# openTPM-v36.net
KiCad netlist of a schematic drawn in EAGLE
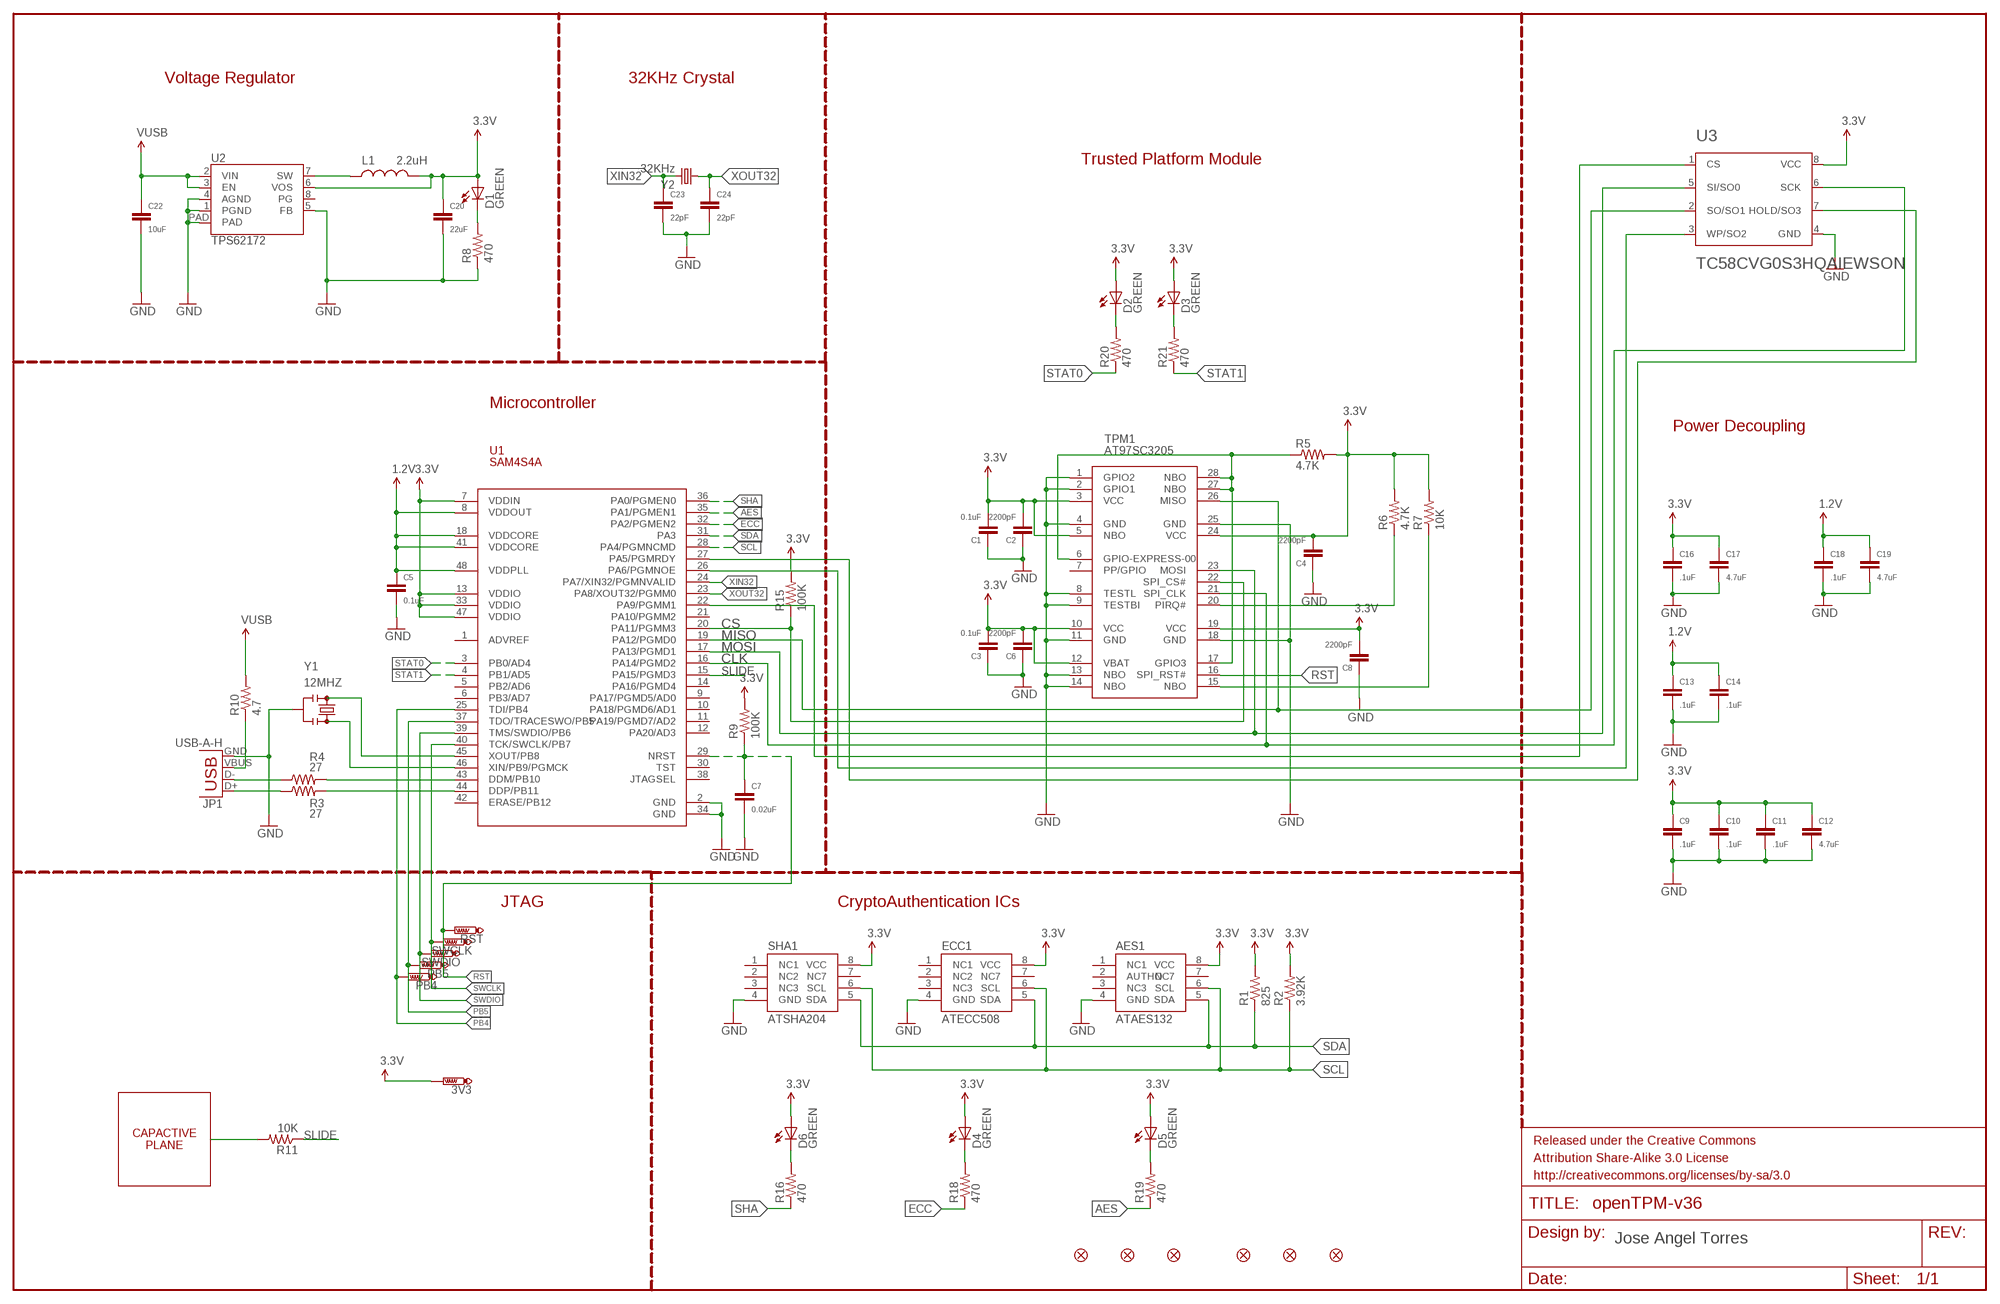
[diagram p0: schematic, sheet 1]

(export (version "E")
  (design (tool "Eeschema 10.0.6"))
  (components
    (comp (ref "3V3")
      (value "PTR1B1,27")
      (footprint "eagle-import:B1,27")
      (libsource (lib "eagle-import") (part "PTR1B1,27"))
    )
    (comp (ref "AES1")
      (value "ATAES132")
      (footprint "eagle-import:CRYPTOTRONIX_SOIC8")
      (libsource (lib "eagle-import") (part "CRYPTOTRONIX_ATAES132"))
    )
    (comp (ref "C1")
      (value "0.1uF")
      (footprint "eagle-import:0402")
      (libsource (lib "eagle-import") (part "CAPACITOR.0402"))
    )
    (comp (ref "C2")
      (value "2200pF")
      (footprint "eagle-import:0402")
      (libsource (lib "eagle-import") (part "CAPACITOR.0402"))
    )
    (comp (ref "C3")
      (value "0.1uF")
      (footprint "eagle-import:0402")
      (libsource (lib "eagle-import") (part "CAPACITOR.0402"))
    )
    (comp (ref "C4")
      (value "2200pF")
      (footprint "eagle-import:0402")
      (libsource (lib "eagle-import") (part "CAPACITOR.0402"))
    )
    (comp (ref "C5")
      (value "0.1uF")
      (footprint "eagle-import:0402")
      (libsource (lib "eagle-import") (part "CAPACITOR.0402"))
    )
    (comp (ref "C6")
      (value "2200pF")
      (footprint "eagle-import:0402")
      (libsource (lib "eagle-import") (part "CAPACITOR.0402"))
    )
    (comp (ref "C7")
      (value "0.02uF")
      (footprint "eagle-import:0402")
      (libsource (lib "eagle-import") (part "CAPACITOR.0402"))
    )
    (comp (ref "C8")
      (value "2200pF")
      (footprint "eagle-import:0402")
      (libsource (lib "eagle-import") (part "CAPACITOR.0402"))
    )
    (comp (ref "C9")
      (value ".1uF")
      (footprint "eagle-import:0402")
      (libsource (lib "eagle-import") (part "CAPACITOR.0402"))
    )
    (comp (ref "C10")
      (value ".1uF")
      (footprint "eagle-import:0402")
      (libsource (lib "eagle-import") (part "CAPACITOR.0402"))
    )
    (comp (ref "C11")
      (value ".1uF")
      (footprint "eagle-import:0402")
      (libsource (lib "eagle-import") (part "CAPACITOR.0402"))
    )
    (comp (ref "C12")
      (value "4.7uF")
      (footprint "eagle-import:0402")
      (libsource (lib "eagle-import") (part "CAPACITOR.0402"))
    )
    (comp (ref "C13")
      (value ".1uF")
      (footprint "eagle-import:0402")
      (libsource (lib "eagle-import") (part "CAPACITOR.0402"))
    )
    (comp (ref "C14")
      (value ".1uF")
      (footprint "eagle-import:0402")
      (libsource (lib "eagle-import") (part "CAPACITOR.0402"))
    )
    (comp (ref "C16")
      (value ".1uF")
      (footprint "eagle-import:0402")
      (libsource (lib "eagle-import") (part "CAPACITOR.0402"))
    )
    (comp (ref "C17")
      (value "4.7uF")
      (footprint "eagle-import:0402")
      (libsource (lib "eagle-import") (part "CAPACITOR.0402"))
    )
    (comp (ref "C18")
      (value ".1uF")
      (footprint "eagle-import:0402")
      (libsource (lib "eagle-import") (part "CAPACITOR.0402"))
    )
    (comp (ref "C19")
      (value "4.7uF")
      (footprint "eagle-import:0402")
      (libsource (lib "eagle-import") (part "CAPACITOR.0402"))
    )
    (comp (ref "C20")
      (value "22uF")
      (footprint "eagle-import:0603")
      (libsource (lib "eagle-import") (part "CAPACITOR.0603"))
    )
    (comp (ref "C22")
      (value "10uF")
      (footprint "eagle-import:0402")
      (libsource (lib "eagle-import") (part "CAPACITOR.0402"))
    )
    (comp (ref "C23")
      (value "22pF")
      (footprint "eagle-import:0402")
      (libsource (lib "eagle-import") (part "CAPACITOR.0402"))
    )
    (comp (ref "C24")
      (value "22pF")
      (footprint "eagle-import:0402")
      (libsource (lib "eagle-import") (part "CAPACITOR.0402"))
    )
    (comp (ref "D1")
      (value "GREEN")
      (footprint "eagle-import:SPARKFUN-LED_LED-0603")
      (libsource (lib "eagle-import") (part "SPARKFUN-LED_LED-GREEN0603"))
    )
    (comp (ref "D2")
      (value "GREEN")
      (footprint "eagle-import:SPARKFUN-LED_LED-0603")
      (libsource (lib "eagle-import") (part "SPARKFUN-LED_LED-GREEN0603"))
    )
    (comp (ref "D3")
      (value "GREEN")
      (footprint "eagle-import:SPARKFUN-LED_LED-0603")
      (libsource (lib "eagle-import") (part "SPARKFUN-LED_LED-GREEN0603"))
    )
    (comp (ref "D4")
      (value "GREEN")
      (footprint "eagle-import:SPARKFUN-LED_LED-0603")
      (libsource (lib "eagle-import") (part "SPARKFUN-LED_LED-GREEN0603"))
    )
    (comp (ref "D5")
      (value "GREEN")
      (footprint "eagle-import:SPARKFUN-LED_LED-0603")
      (libsource (lib "eagle-import") (part "SPARKFUN-LED_LED-GREEN0603"))
    )
    (comp (ref "D6")
      (value "GREEN")
      (footprint "eagle-import:SPARKFUN-LED_LED-0603")
      (libsource (lib "eagle-import") (part "SPARKFUN-LED_LED-GREEN0603"))
    )
    (comp (ref "ECC1")
      (value "ATECC508")
      (footprint "eagle-import:CRYPTOTRONIX_SOIC8")
      (libsource (lib "eagle-import") (part "ATECC508"))
    )
    (comp (ref "FID1")
      (value "SPARKFUN-AESTHETICS_FIDUCIAL1X2")
      (footprint "eagle-import:SPARKFUN-AESTHETICS_FIDUCIAL-1X2")
      (libsource (lib "eagle-import") (part "SPARKFUN-AESTHETICS_FIDUCIAL1X2"))
    )
    (comp (ref "FID2")
      (value "SPARKFUN-AESTHETICS_FIDUCIAL1X2")
      (footprint "eagle-import:SPARKFUN-AESTHETICS_FIDUCIAL-1X2")
      (libsource (lib "eagle-import") (part "SPARKFUN-AESTHETICS_FIDUCIAL1X2"))
    )
    (comp (ref "FID3")
      (value "SPARKFUN-AESTHETICS_FIDUCIAL1X2")
      (footprint "eagle-import:SPARKFUN-AESTHETICS_FIDUCIAL-1X2")
      (libsource (lib "eagle-import") (part "SPARKFUN-AESTHETICS_FIDUCIAL1X2"))
    )
    (comp (ref "FID4")
      (value "SPARKFUN-AESTHETICS_FIDUCIAL1X2")
      (footprint "eagle-import:SPARKFUN-AESTHETICS_FIDUCIAL-1X2")
      (libsource (lib "eagle-import") (part "SPARKFUN-AESTHETICS_FIDUCIAL1X2"))
    )
    (comp (ref "FID5")
      (value "SPARKFUN-AESTHETICS_FIDUCIAL1X2")
      (footprint "eagle-import:SPARKFUN-AESTHETICS_FIDUCIAL-1X2")
      (libsource (lib "eagle-import") (part "SPARKFUN-AESTHETICS_FIDUCIAL1X2"))
    )
    (comp (ref "FID6")
      (value "SPARKFUN-AESTHETICS_FIDUCIAL1X2")
      (footprint "eagle-import:SPARKFUN-AESTHETICS_FIDUCIAL-1X2")
      (libsource (lib "eagle-import") (part "SPARKFUN-AESTHETICS_FIDUCIAL1X2"))
    )
    (comp (ref "JP1")
      (value "USB-A-H")
      (footprint "eagle-import:USB-A-H")
      (libsource (lib "eagle-import") (part "USB-A-H"))
    )
    (comp (ref "L1")
      (value "2.2uH")
      (footprint "eagle-import:C0402")
      (libsource (lib "eagle-import") (part "INDUCTOR0402"))
    )
    (comp (ref "PB4")
      (value "PTR1B1,27")
      (footprint "eagle-import:B1,27")
      (libsource (lib "eagle-import") (part "PTR1B1,27"))
    )
    (comp (ref "PB5")
      (value "PTR1B1,27")
      (footprint "eagle-import:B1,27")
      (libsource (lib "eagle-import") (part "PTR1B1,27"))
    )
    (comp (ref "R1")
      (value "825")
      (footprint "eagle-import:0402")
      (libsource (lib "eagle-import") (part "RESISTOR.0402"))
    )
    (comp (ref "R2")
      (value "3.92K")
      (footprint "eagle-import:0402")
      (libsource (lib "eagle-import") (part "RESISTOR.0402"))
    )
    (comp (ref "R3")
      (value "27")
      (footprint "eagle-import:0402")
      (libsource (lib "eagle-import") (part "RESISTOR.0402"))
    )
    (comp (ref "R4")
      (value "27")
      (footprint "eagle-import:0402")
      (libsource (lib "eagle-import") (part "RESISTOR.0402"))
    )
    (comp (ref "R5")
      (value "4.7K")
      (footprint "eagle-import:0402")
      (libsource (lib "eagle-import") (part "RESISTOR.0402"))
    )
    (comp (ref "R6")
      (value "4.7K")
      (footprint "eagle-import:0402")
      (libsource (lib "eagle-import") (part "RESISTOR.0402"))
    )
    (comp (ref "R7")
      (value "10K")
      (footprint "eagle-import:0402")
      (libsource (lib "eagle-import") (part "RESISTOR.0402"))
    )
    (comp (ref "R8")
      (value "470")
      (footprint "eagle-import:0402")
      (libsource (lib "eagle-import") (part "RESISTOR.0402"))
    )
    (comp (ref "R9")
      (value "100K")
      (footprint "eagle-import:0402")
      (libsource (lib "eagle-import") (part "RESISTOR.0402"))
    )
    (comp (ref "R10")
      (value "4.7")
      (footprint "eagle-import:0402")
      (libsource (lib "eagle-import") (part "RESISTOR.0402"))
    )
    (comp (ref "R11")
      (value "10K")
      (footprint "eagle-import:0402")
      (libsource (lib "eagle-import") (part "RESISTOR.0402"))
    )
    (comp (ref "R15")
      (value "100K")
      (footprint "eagle-import:0402")
      (libsource (lib "eagle-import") (part "RESISTOR.0402"))
    )
    (comp (ref "R16")
      (value "470")
      (footprint "eagle-import:0402")
      (libsource (lib "eagle-import") (part "RESISTOR.0402"))
    )
    (comp (ref "R18")
      (value "470")
      (footprint "eagle-import:0402")
      (libsource (lib "eagle-import") (part "RESISTOR.0402"))
    )
    (comp (ref "R19")
      (value "470")
      (footprint "eagle-import:0402")
      (libsource (lib "eagle-import") (part "RESISTOR.0402"))
    )
    (comp (ref "R20")
      (value "470")
      (footprint "eagle-import:0402")
      (libsource (lib "eagle-import") (part "RESISTOR.0402"))
    )
    (comp (ref "R21")
      (value "470")
      (footprint "eagle-import:0402")
      (libsource (lib "eagle-import") (part "RESISTOR.0402"))
    )
    (comp (ref "RST")
      (value "PTR1B1,27")
      (footprint "eagle-import:B1,27")
      (libsource (lib "eagle-import") (part "PTR1B1,27"))
    )
    (comp (ref "SHA1")
      (value "ATSHA204")
      (footprint "eagle-import:CRYPTOTRONIX_SOIC8")
      (libsource (lib "eagle-import") (part "CRYPTOTRONIX_ATSHA204"))
    )
    (comp (ref "SWCLK")
      (value "PTR1B1,27")
      (footprint "eagle-import:B1,27")
      (libsource (lib "eagle-import") (part "PTR1B1,27"))
    )
    (comp (ref "SWDIO")
      (value "PTR1B1,27")
      (footprint "eagle-import:B1,27")
      (libsource (lib "eagle-import") (part "PTR1B1,27"))
    )
    (comp (ref "TPM1")
      (value "AT97SC3205")
      (footprint "eagle-import:TSSOP28")
      (libsource (lib "eagle-import") (part "AT97SC3205"))
    )
    (comp (ref "U1")
      (value "SAM4S4A")
      (footprint "eagle-import:LQFP-48")
      (libsource (lib "eagle-import") (part "SAM4S4A"))
    )
    (comp (ref "U2")
      (value "TPS62172")
      (footprint "eagle-import:WSON-8-PAD")
      (libsource (lib "eagle-import") (part "TPS62172"))
    )
    (comp (ref "U3")
      (value "TC58CVG0S3HQAIEWSON")
      (footprint "eagle-import:WSON-8-PAD")
      (libsource (lib "eagle-import") (part "TC58CVG0S3HQAIEWSON"))
    )
    (comp (ref "Y1")
      (value "12MHZ")
      (footprint "eagle-import:RESONATOR-SMD")
      (libsource (lib "eagle-import") (part "RESONATOR12MHZ"))
    )
    (comp (ref "Y2")
      (value "32KHz")
      (footprint "eagle-import:CRYSTAL-32KHZ-SMD_EPSON_MC146")
      (libsource (lib "eagle-import") (part "CRYSTALEPSONMC146"))
    )
  )
  (nets
    (net (code "1") (name "/CLK") (class "Default")
      (node (ref "TPM1") (pin "21") (pinfunction "SPI_CLK_21") (pintype "bidirectional"))
      (node (ref "U1") (pin "16") (pinfunction "PA14/PGMD2_16") (pintype "bidirectional"))
      (node (ref "U3") (pin "6") (pinfunction "SCK_6") (pintype "bidirectional"))
    )
    (net (code "2") (name "/CS") (class "Default")
      (node (ref "R15") (pin "1") (pinfunction "1_1") (pintype "passive"))
      (node (ref "TPM1") (pin "22") (pinfunction "SPI_CS#_22") (pintype "power_in"))
      (node (ref "U1") (pin "20") (pinfunction "PA11/PGMM3_20") (pintype "bidirectional"))
    )
    (net (code "3") (name "/MISO") (class "Default")
      (node (ref "TPM1") (pin "26") (pinfunction "MISO_26") (pintype "power_in"))
      (node (ref "U1") (pin "19") (pinfunction "PA12/PGMD0_19") (pintype "bidirectional"))
      (node (ref "U3") (pin "2") (pinfunction "SO/SO1_2") (pintype "bidirectional"))
    )
    (net (code "4") (name "/MOSI") (class "Default")
      (node (ref "TPM1") (pin "23") (pinfunction "MOSI_23") (pintype "power_in"))
      (node (ref "U1") (pin "17") (pinfunction "PA13/PGMD1_17") (pintype "bidirectional"))
      (node (ref "U3") (pin "5") (pinfunction "SI/SO0_5") (pintype "bidirectional"))
    )
    (net (code "5") (name "/SLIDE") (class "Default")
      (node (ref "R11") (pin "1") (pinfunction "1_1") (pintype "passive"))
      (node (ref "U1") (pin "15") (pinfunction "PA15/PGMD3_15") (pintype "bidirectional"))
    )
    (net (code "6") (name "1.2V") (class "Default")
      (node (ref "C13") (pin "1") (pinfunction "1_1") (pintype "passive"))
      (node (ref "C14") (pin "1") (pinfunction "1_1") (pintype "passive"))
      (node (ref "C18") (pin "1") (pinfunction "1_1") (pintype "passive"))
      (node (ref "C19") (pin "1") (pinfunction "1_1") (pintype "passive"))
      (node (ref "C5") (pin "1") (pinfunction "1_1") (pintype "passive"))
      (node (ref "U1") (pin "18") (pinfunction "VDDCORE_18") (pintype "bidirectional"))
      (node (ref "U1") (pin "41") (pinfunction "VDDCORE_41") (pintype "bidirectional"))
      (node (ref "U1") (pin "48") (pinfunction "VDDPLL_48") (pintype "bidirectional"))
      (node (ref "U1") (pin "8") (pinfunction "VDDOUT_8") (pintype "bidirectional"))
    )
    (net (code "7") (name "3.3V") (class "Default")
      (node (ref "3V3") (pin "TP") (pinfunction "TP_TP") (pintype "input"))
      (node (ref "AES1") (pin "8") (pinfunction "VCC_8") (pintype "power_in"))
      (node (ref "C1") (pin "2") (pinfunction "2_2") (pintype "passive"))
      (node (ref "C10") (pin "1") (pinfunction "1_1") (pintype "passive"))
      (node (ref "C11") (pin "1") (pinfunction "1_1") (pintype "passive"))
      (node (ref "C12") (pin "1") (pinfunction "1_1") (pintype "passive"))
      (node (ref "C16") (pin "1") (pinfunction "1_1") (pintype "passive"))
      (node (ref "C17") (pin "1") (pinfunction "1_1") (pintype "passive"))
      (node (ref "C2") (pin "2") (pinfunction "2_2") (pintype "passive"))
      (node (ref "C20") (pin "1") (pinfunction "1_1") (pintype "passive"))
      (node (ref "C3") (pin "2") (pinfunction "2_2") (pintype "passive"))
      (node (ref "C4") (pin "2") (pinfunction "2_2") (pintype "passive"))
      (node (ref "C6") (pin "2") (pinfunction "2_2") (pintype "passive"))
      (node (ref "C8") (pin "2") (pinfunction "2_2") (pintype "passive"))
      (node (ref "C9") (pin "1") (pinfunction "1_1") (pintype "passive"))
      (node (ref "D1") (pin "A") (pinfunction "A_A") (pintype "passive"))
      (node (ref "D2") (pin "A") (pinfunction "A_A") (pintype "passive"))
      (node (ref "D3") (pin "A") (pinfunction "A_A") (pintype "passive"))
      (node (ref "D4") (pin "A") (pinfunction "A_A") (pintype "passive"))
      (node (ref "D5") (pin "A") (pinfunction "A_A") (pintype "passive"))
      (node (ref "D6") (pin "A") (pinfunction "A_A") (pintype "passive"))
      (node (ref "ECC1") (pin "8") (pinfunction "VCC_8") (pintype "power_in"))
      (node (ref "L1") (pin "2") (pinfunction "2_2") (pintype "passive"))
      (node (ref "R1") (pin "2") (pinfunction "2_2") (pintype "passive"))
      (node (ref "R15") (pin "2") (pinfunction "2_2") (pintype "passive"))
      (node (ref "R2") (pin "2") (pinfunction "2_2") (pintype "passive"))
      (node (ref "R5") (pin "2") (pinfunction "2_2") (pintype "passive"))
      (node (ref "R6") (pin "2") (pinfunction "2_2") (pintype "passive"))
      (node (ref "R7") (pin "2") (pinfunction "2_2") (pintype "passive"))
      (node (ref "R9") (pin "2") (pinfunction "2_2") (pintype "passive"))
      (node (ref "SHA1") (pin "8") (pinfunction "VCC_8") (pintype "power_in"))
      (node (ref "TPM1") (pin "10") (pinfunction "VCC_10") (pintype "power_in"))
      (node (ref "TPM1") (pin "12") (pinfunction "VBAT_12") (pintype "bidirectional"))
      (node (ref "TPM1") (pin "19") (pinfunction "VCC_19") (pintype "power_in"))
      (node (ref "TPM1") (pin "24") (pinfunction "VCC_24") (pintype "power_in"))
      (node (ref "TPM1") (pin "3") (pinfunction "VCC_3") (pintype "power_in"))
      (node (ref "TPM1") (pin "5") (pinfunction "NBO_5") (pintype "bidirectional"))
      (node (ref "U1") (pin "13") (pinfunction "VDDIO_13") (pintype "bidirectional"))
      (node (ref "U1") (pin "33") (pinfunction "VDDIO_33") (pintype "bidirectional"))
      (node (ref "U1") (pin "47") (pinfunction "VDDIO_47") (pintype "bidirectional"))
      (node (ref "U1") (pin "7") (pinfunction "VDDIN_7") (pintype "bidirectional"))
      (node (ref "U2") (pin "6") (pinfunction "VOS_6") (pintype "bidirectional"))
      (node (ref "U3") (pin "8") (pinfunction "VCC_8") (pintype "bidirectional"))
    )
    (net (code "8") (name "AES") (class "Default")
      (node (ref "R19") (pin "1") (pinfunction "1_1") (pintype "passive"))
      (node (ref "U1") (pin "35") (pinfunction "PA1/PGMEN1_35") (pintype "bidirectional"))
    )
    (net (code "9") (name "ECC") (class "Default")
      (node (ref "R18") (pin "1") (pinfunction "1_1") (pintype "passive"))
      (node (ref "U1") (pin "32") (pinfunction "PA2/PGMEN2_32") (pintype "bidirectional"))
    )
    (net (code "10") (name "GND") (class "Default")
      (node (ref "AES1") (pin "4") (pinfunction "GND_4") (pintype "power_in"))
      (node (ref "C1") (pin "1") (pinfunction "1_1") (pintype "passive"))
      (node (ref "C10") (pin "2") (pinfunction "2_2") (pintype "passive"))
      (node (ref "C11") (pin "2") (pinfunction "2_2") (pintype "passive"))
      (node (ref "C12") (pin "2") (pinfunction "2_2") (pintype "passive"))
      (node (ref "C13") (pin "2") (pinfunction "2_2") (pintype "passive"))
      (node (ref "C14") (pin "2") (pinfunction "2_2") (pintype "passive"))
      (node (ref "C16") (pin "2") (pinfunction "2_2") (pintype "passive"))
      (node (ref "C17") (pin "2") (pinfunction "2_2") (pintype "passive"))
      (node (ref "C18") (pin "2") (pinfunction "2_2") (pintype "passive"))
      (node (ref "C19") (pin "2") (pinfunction "2_2") (pintype "passive"))
      (node (ref "C2") (pin "1") (pinfunction "1_1") (pintype "passive"))
      (node (ref "C20") (pin "2") (pinfunction "2_2") (pintype "passive"))
      (node (ref "C22") (pin "2") (pinfunction "2_2") (pintype "passive"))
      (node (ref "C23") (pin "2") (pinfunction "2_2") (pintype "passive"))
      (node (ref "C24") (pin "2") (pinfunction "2_2") (pintype "passive"))
      (node (ref "C3") (pin "1") (pinfunction "1_1") (pintype "passive"))
      (node (ref "C4") (pin "1") (pinfunction "1_1") (pintype "passive"))
      (node (ref "C5") (pin "2") (pinfunction "2_2") (pintype "passive"))
      (node (ref "C6") (pin "1") (pinfunction "1_1") (pintype "passive"))
      (node (ref "C7") (pin "2") (pinfunction "2_2") (pintype "passive"))
      (node (ref "C8") (pin "1") (pinfunction "1_1") (pintype "passive"))
      (node (ref "C9") (pin "2") (pinfunction "2_2") (pintype "passive"))
      (node (ref "ECC1") (pin "4") (pinfunction "GND_4") (pintype "power_in"))
      (node (ref "JP1") (pin "GND") (pinfunction "GND_GND") (pintype "bidirectional"))
      (node (ref "R8") (pin "1") (pinfunction "1_1") (pintype "passive"))
      (node (ref "SHA1") (pin "4") (pinfunction "GND_4") (pintype "power_in"))
      (node (ref "TPM1") (pin "1") (pinfunction "GPIO2_1") (pintype "bidirectional"))
      (node (ref "TPM1") (pin "11") (pinfunction "GND_11") (pintype "power_in"))
      (node (ref "TPM1") (pin "13") (pinfunction "NBO_13") (pintype "bidirectional"))
      (node (ref "TPM1") (pin "14") (pinfunction "NBO_14") (pintype "bidirectional"))
      (node (ref "TPM1") (pin "18") (pinfunction "GND_18") (pintype "power_in"))
      (node (ref "TPM1") (pin "2") (pinfunction "GPIO1_2") (pintype "bidirectional"))
      (node (ref "TPM1") (pin "25") (pinfunction "GND_25") (pintype "power_in"))
      (node (ref "TPM1") (pin "4") (pinfunction "GND_4") (pintype "power_in"))
      (node (ref "TPM1") (pin "8") (pinfunction "TESTL_8") (pintype "bidirectional"))
      (node (ref "TPM1") (pin "9") (pinfunction "TESTBI_9") (pintype "bidirectional"))
      (node (ref "U1") (pin "2") (pinfunction "GND_2") (pintype "bidirectional"))
      (node (ref "U1") (pin "34") (pinfunction "GND_34") (pintype "bidirectional"))
      (node (ref "U2") (pin "1") (pinfunction "PGND_1") (pintype "bidirectional"))
      (node (ref "U2") (pin "4") (pinfunction "AGND_4") (pintype "bidirectional"))
      (node (ref "U2") (pin "5") (pinfunction "FB_5") (pintype "bidirectional"))
      (node (ref "U2") (pin "PAD") (pinfunction "PAD_PAD") (pintype "bidirectional"))
      (node (ref "U3") (pin "4") (pinfunction "GND_4") (pintype "bidirectional"))
      (node (ref "Y1") (pin "2") (pinfunction "2_2") (pintype "passive"))
    )
    (net (code "11") (name "Net-(D1-PadC)") (class "Default")
      (node (ref "D1") (pin "C") (pinfunction "C_C") (pintype "passive"))
      (node (ref "R8") (pin "2") (pinfunction "2_2") (pintype "passive"))
    )
    (net (code "12") (name "Net-(D2-PadC)") (class "Default")
      (node (ref "D2") (pin "C") (pinfunction "C_C") (pintype "passive"))
      (node (ref "R20") (pin "2") (pinfunction "2_2") (pintype "passive"))
    )
    (net (code "13") (name "Net-(D3-PadC)") (class "Default")
      (node (ref "D3") (pin "C") (pinfunction "C_C") (pintype "passive"))
      (node (ref "R21") (pin "2") (pinfunction "2_2") (pintype "passive"))
    )
    (net (code "14") (name "Net-(D4-PadC)") (class "Default")
      (node (ref "D4") (pin "C") (pinfunction "C_C") (pintype "passive"))
      (node (ref "R18") (pin "2") (pinfunction "2_2") (pintype "passive"))
    )
    (net (code "15") (name "Net-(D5-PadC)") (class "Default")
      (node (ref "D5") (pin "C") (pinfunction "C_C") (pintype "passive"))
      (node (ref "R19") (pin "2") (pinfunction "2_2") (pintype "passive"))
    )
    (net (code "16") (name "Net-(D6-PadC)") (class "Default")
      (node (ref "D6") (pin "C") (pinfunction "C_C") (pintype "passive"))
      (node (ref "R16") (pin "2") (pinfunction "2_2") (pintype "passive"))
    )
    (net (code "17") (name "Net-(JP1-PadD+)") (class "Default")
      (node (ref "JP1") (pin "D+") (pinfunction "D+_D+") (pintype "bidirectional"))
      (node (ref "R3") (pin "1") (pinfunction "1_1") (pintype "passive"))
    )
    (net (code "18") (name "Net-(JP1-PadD-)") (class "Default")
      (node (ref "JP1") (pin "D-") (pinfunction "D-_D-") (pintype "bidirectional"))
      (node (ref "R4") (pin "1") (pinfunction "1_1") (pintype "passive"))
    )
    (net (code "19") (name "Net-(JP1-PadVBUS)") (class "Default")
      (node (ref "JP1") (pin "VBUS") (pinfunction "VBUS_VBUS") (pintype "bidirectional"))
      (node (ref "R10") (pin "1") (pinfunction "1_1") (pintype "passive"))
    )
    (net (code "20") (name "Net-(R7-Pad1)") (class "Default")
      (node (ref "R7") (pin "1") (pinfunction "1_1") (pintype "passive"))
      (node (ref "TPM1") (pin "15") (pinfunction "NBO_15") (pintype "bidirectional"))
    )
    (net (code "21") (name "Net-(TPM1-GPIO-EXPRESS-00)") (class "Default")
      (node (ref "R5") (pin "1") (pinfunction "1_1") (pintype "passive"))
      (node (ref "TPM1") (pin "17") (pinfunction "GPIO3_17") (pintype "power_in"))
      (node (ref "TPM1") (pin "27") (pinfunction "NBO_27") (pintype "bidirectional"))
      (node (ref "TPM1") (pin "28") (pinfunction "NBO_28") (pintype "bidirectional"))
      (node (ref "TPM1") (pin "6") (pinfunction "GPIO-EXPRESS-00_6") (pintype "power_in"))
    )
    (net (code "22") (name "Net-(TPM1-PIRQ#)") (class "Default")
      (node (ref "R6") (pin "1") (pinfunction "1_1") (pintype "passive"))
      (node (ref "TPM1") (pin "20") (pinfunction "PIRQ#_20") (pintype "power_in"))
    )
    (net (code "23") (name "Net-(U1-DDM{slash}PB10)") (class "Default")
      (node (ref "R4") (pin "2") (pinfunction "2_2") (pintype "passive"))
      (node (ref "U1") (pin "43") (pinfunction "DDM/PB10_43") (pintype "bidirectional"))
    )
    (net (code "24") (name "Net-(U1-DDP{slash}PB11)") (class "Default")
      (node (ref "R3") (pin "2") (pinfunction "2_2") (pintype "passive"))
      (node (ref "U1") (pin "44") (pinfunction "DDP/PB11_44") (pintype "bidirectional"))
    )
    (net (code "25") (name "Net-(U1-PA5{slash}PGMRDY)") (class "Default")
      (node (ref "U1") (pin "27") (pinfunction "PA5/PGMRDY_27") (pintype "bidirectional"))
      (node (ref "U3") (pin "7") (pinfunction "HOLD/SO3_7") (pintype "bidirectional"))
    )
    (net (code "26") (name "Net-(U1-PA6{slash}PGMNOE)") (class "Default")
      (node (ref "U1") (pin "26") (pinfunction "PA6/PGMNOE_26") (pintype "bidirectional"))
      (node (ref "U3") (pin "3") (pinfunction "WP/SO2_3") (pintype "bidirectional"))
    )
    (net (code "27") (name "Net-(U1-PA9{slash}PGMM1)") (class "Default")
      (node (ref "U1") (pin "22") (pinfunction "PA9/PGMM1_22") (pintype "bidirectional"))
      (node (ref "U3") (pin "1") (pinfunction "CS_1") (pintype "bidirectional"))
    )
    (net (code "28") (name "Net-(U1-XIN{slash}PB9{slash}PGMCK)") (class "Default")
      (node (ref "U1") (pin "46") (pinfunction "XIN/PB9/PGMCK_46") (pintype "bidirectional"))
      (node (ref "Y1") (pin "3") (pinfunction "3_3") (pintype "passive"))
    )
    (net (code "29") (name "Net-(U1-XOUT{slash}PB8)") (class "Default")
      (node (ref "U1") (pin "45") (pinfunction "XOUT/PB8_45") (pintype "bidirectional"))
      (node (ref "Y1") (pin "1") (pinfunction "1_1") (pintype "passive"))
    )
    (net (code "30") (name "Net-(U2-SW)") (class "Default")
      (node (ref "L1") (pin "1") (pinfunction "1_1") (pintype "passive"))
      (node (ref "U2") (pin "7") (pinfunction "SW_7") (pintype "bidirectional"))
    )
    (net (code "31") (name "PB4") (class "Default")
      (node (ref "PB4") (pin "TP") (pinfunction "TP_TP") (pintype "input"))
      (node (ref "U1") (pin "25") (pinfunction "TDI/PB4_25") (pintype "bidirectional"))
    )
    (net (code "32") (name "PB5") (class "Default")
      (node (ref "PB5") (pin "TP") (pinfunction "TP_TP") (pintype "input"))
      (node (ref "U1") (pin "37") (pinfunction "TDO/TRACESWO/PB5_37") (pintype "bidirectional"))
    )
    (net (code "33") (name "RST") (class "Default")
      (node (ref "C7") (pin "1") (pinfunction "1_1") (pintype "passive"))
      (node (ref "R9") (pin "1") (pinfunction "1_1") (pintype "passive"))
      (node (ref "RST") (pin "TP") (pinfunction "TP_TP") (pintype "input"))
      (node (ref "TPM1") (pin "16") (pinfunction "SPI_RST#_16") (pintype "bidirectional"))
      (node (ref "U1") (pin "29") (pinfunction "NRST_29") (pintype "bidirectional"))
    )
    (net (code "34") (name "SCL") (class "Default")
      (node (ref "AES1") (pin "6") (pinfunction "SCL_6") (pintype "bidirectional"))
      (node (ref "ECC1") (pin "6") (pinfunction "SCL_6") (pintype "bidirectional"))
      (node (ref "R2") (pin "1") (pinfunction "1_1") (pintype "passive"))
      (node (ref "SHA1") (pin "6") (pinfunction "SCL_6") (pintype "bidirectional"))
      (node (ref "U1") (pin "28") (pinfunction "PA4/PGMNCMD_28") (pintype "bidirectional"))
    )
    (net (code "35") (name "SDA") (class "Default")
      (node (ref "AES1") (pin "5") (pinfunction "SDA_5") (pintype "bidirectional"))
      (node (ref "ECC1") (pin "5") (pinfunction "SDA_5") (pintype "bidirectional"))
      (node (ref "R1") (pin "1") (pinfunction "1_1") (pintype "passive"))
      (node (ref "SHA1") (pin "5") (pinfunction "SDA_5") (pintype "bidirectional"))
      (node (ref "U1") (pin "31") (pinfunction "PA3_31") (pintype "bidirectional"))
    )
    (net (code "36") (name "SHA") (class "Default")
      (node (ref "R16") (pin "1") (pinfunction "1_1") (pintype "passive"))
      (node (ref "U1") (pin "36") (pinfunction "PA0/PGMEN0_36") (pintype "bidirectional"))
    )
    (net (code "37") (name "STAT0") (class "Default")
      (node (ref "R20") (pin "1") (pinfunction "1_1") (pintype "passive"))
      (node (ref "U1") (pin "3") (pinfunction "PB0/AD4_3") (pintype "bidirectional"))
    )
    (net (code "38") (name "STAT1") (class "Default")
      (node (ref "R21") (pin "1") (pinfunction "1_1") (pintype "passive"))
      (node (ref "U1") (pin "4") (pinfunction "PB1/AD5_4") (pintype "bidirectional"))
    )
    (net (code "39") (name "SWCLK") (class "Default")
      (node (ref "SWCLK") (pin "TP") (pinfunction "TP_TP") (pintype "input"))
      (node (ref "U1") (pin "40") (pinfunction "TCK/SWCLK/PB7_40") (pintype "bidirectional"))
    )
    (net (code "40") (name "SWDIO") (class "Default")
      (node (ref "SWDIO") (pin "TP") (pinfunction "TP_TP") (pintype "input"))
      (node (ref "U1") (pin "39") (pinfunction "TMS/SWDIO/PB6_39") (pintype "bidirectional"))
    )
    (net (code "41") (name "VUSB") (class "Default")
      (node (ref "C22") (pin "1") (pinfunction "1_1") (pintype "passive"))
      (node (ref "R10") (pin "2") (pinfunction "2_2") (pintype "passive"))
      (node (ref "U2") (pin "2") (pinfunction "VIN_2") (pintype "bidirectional"))
      (node (ref "U2") (pin "3") (pinfunction "EN_3") (pintype "bidirectional"))
    )
    (net (code "42") (name "XIN32") (class "Default")
      (node (ref "C23") (pin "1") (pinfunction "1_1") (pintype "passive"))
      (node (ref "U1") (pin "24") (pinfunction "PA7/XIN32/PGMNVALID_24") (pintype "bidirectional"))
      (node (ref "Y2") (pin "P$1") (pinfunction "2_P$1") (pintype "passive"))
    )
    (net (code "43") (name "XOUT32") (class "Default")
      (node (ref "C24") (pin "1") (pinfunction "1_1") (pintype "passive"))
      (node (ref "U1") (pin "23") (pinfunction "PA8/XOUT32/PGMM0_23") (pintype "bidirectional"))
      (node (ref "Y2") (pin "P$2") (pinfunction "1_P$2") (pintype "passive"))
    )
    (net (code "44") (name "unconnected-(AES1-AUTHO-Pad2)") (class "Default")
      (node (ref "AES1") (pin "2") (pinfunction "AUTHO_2") (pintype "bidirectional"))
    )
    (net (code "45") (name "unconnected-(AES1-NC1-Pad1)") (class "Default")
      (node (ref "AES1") (pin "1") (pinfunction "NC1_1") (pintype "no_connect"))
    )
    (net (code "46") (name "unconnected-(AES1-NC3-Pad3)") (class "Default")
      (node (ref "AES1") (pin "3") (pinfunction "NC3_3") (pintype "no_connect"))
    )
    (net (code "47") (name "unconnected-(AES1-NC7-Pad7)") (class "Default")
      (node (ref "AES1") (pin "7") (pinfunction "NC7_7") (pintype "no_connect"))
    )
    (net (code "48") (name "unconnected-(ECC1-NC1-Pad1)") (class "Default")
      (node (ref "ECC1") (pin "1") (pinfunction "NC1_1") (pintype "bidirectional"))
    )
    (net (code "49") (name "unconnected-(ECC1-NC2-Pad2)") (class "Default")
      (node (ref "ECC1") (pin "2") (pinfunction "NC2_2") (pintype "no_connect"))
    )
    (net (code "50") (name "unconnected-(ECC1-NC3-Pad3)") (class "Default")
      (node (ref "ECC1") (pin "3") (pinfunction "NC3_3") (pintype "no_connect"))
    )
    (net (code "51") (name "unconnected-(ECC1-NC7-Pad7)") (class "Default")
      (node (ref "ECC1") (pin "7") (pinfunction "NC7_7") (pintype "no_connect"))
    )
    (net (code "52") (name "unconnected-(R11-Pad2)") (class "Default")
      (node (ref "R11") (pin "2") (pinfunction "2_2") (pintype "passive"))
    )
    (net (code "53") (name "unconnected-(SHA1-NC1-Pad1)") (class "Default")
      (node (ref "SHA1") (pin "1") (pinfunction "NC1_1") (pintype "no_connect"))
    )
    (net (code "54") (name "unconnected-(SHA1-NC2-Pad2)") (class "Default")
      (node (ref "SHA1") (pin "2") (pinfunction "NC2_2") (pintype "no_connect"))
    )
    (net (code "55") (name "unconnected-(SHA1-NC3-Pad3)") (class "Default")
      (node (ref "SHA1") (pin "3") (pinfunction "NC3_3") (pintype "no_connect"))
    )
    (net (code "56") (name "unconnected-(SHA1-NC7-Pad7)") (class "Default")
      (node (ref "SHA1") (pin "7") (pinfunction "NC7_7") (pintype "no_connect"))
    )
    (net (code "57") (name "unconnected-(TPM1-PP{slash}GPIO-Pad7)") (class "Default")
      (node (ref "TPM1") (pin "7") (pinfunction "PP/GPIO_7") (pintype "bidirectional"))
    )
    (net (code "58") (name "unconnected-(U1-ADVREF-Pad1)") (class "Default")
      (node (ref "U1") (pin "1") (pinfunction "ADVREF_1") (pintype "bidirectional"))
    )
    (net (code "59") (name "unconnected-(U1-ERASE{slash}PB12-Pad42)") (class "Default")
      (node (ref "U1") (pin "42") (pinfunction "ERASE/PB12_42") (pintype "bidirectional"))
    )
    (net (code "60") (name "unconnected-(U1-JTAGSEL-Pad38)") (class "Default")
      (node (ref "U1") (pin "38") (pinfunction "JTAGSEL_38") (pintype "bidirectional"))
    )
    (net (code "61") (name "unconnected-(U1-PA10{slash}PGMM2-Pad21)") (class "Default")
      (node (ref "U1") (pin "21") (pinfunction "PA10/PGMM2_21") (pintype "bidirectional"))
    )
    (net (code "62") (name "unconnected-(U1-PA16{slash}PGMD4-Pad14)") (class "Default")
      (node (ref "U1") (pin "14") (pinfunction "PA16/PGMD4_14") (pintype "bidirectional"))
    )
    (net (code "63") (name "unconnected-(U1-PA17{slash}PGMD5{slash}AD0-Pad9)") (class "Default")
      (node (ref "U1") (pin "9") (pinfunction "PA17/PGMD5/AD0_9") (pintype "bidirectional"))
    )
    (net (code "64") (name "unconnected-(U1-PA18{slash}PGMD6{slash}AD1-Pad10)") (class "Default")
      (node (ref "U1") (pin "10") (pinfunction "PA18/PGMD6/AD1_10") (pintype "bidirectional"))
    )
    (net (code "65") (name "unconnected-(U1-PA19{slash}PGMD7{slash}AD2-Pad11)") (class "Default")
      (node (ref "U1") (pin "11") (pinfunction "PA19/PGMD7/AD2_11") (pintype "bidirectional"))
    )
    (net (code "66") (name "unconnected-(U1-PA20{slash}AD3-Pad12)") (class "Default")
      (node (ref "U1") (pin "12") (pinfunction "PA20/AD3_12") (pintype "bidirectional"))
    )
    (net (code "67") (name "unconnected-(U1-PB2{slash}AD6-Pad5)") (class "Default")
      (node (ref "U1") (pin "5") (pinfunction "PB2/AD6_5") (pintype "bidirectional"))
    )
    (net (code "68") (name "unconnected-(U1-PB3{slash}AD7-Pad6)") (class "Default")
      (node (ref "U1") (pin "6") (pinfunction "PB3/AD7_6") (pintype "bidirectional"))
    )
    (net (code "69") (name "unconnected-(U1-TST-Pad30)") (class "Default")
      (node (ref "U1") (pin "30") (pinfunction "TST_30") (pintype "bidirectional"))
    )
    (net (code "70") (name "unconnected-(U2-PG-Pad8)") (class "Default")
      (node (ref "U2") (pin "8") (pinfunction "PG_8") (pintype "bidirectional"))
    )
  )
)
